# Output_amplifier.net
KiCad netlist of a schematic drawn in Altium Designer
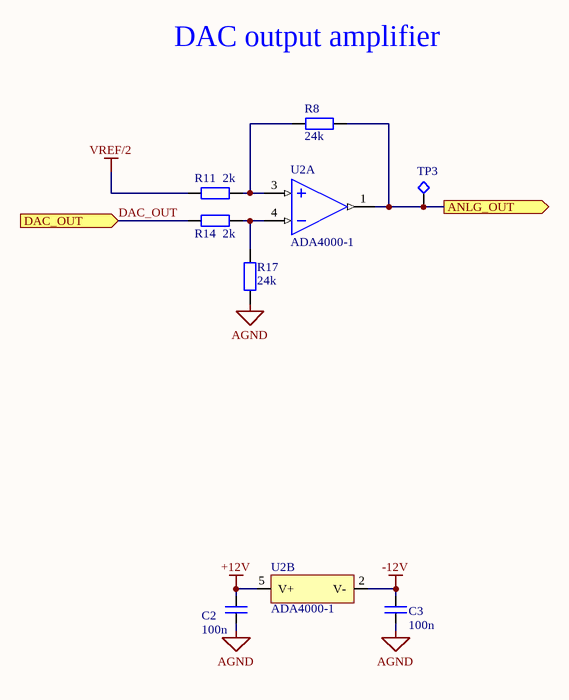
[diagram p0: Output_amplifier.SchDoc]

(export (version "E")
  (design (tool "Eeschema 10.0.6"))
  (components
    (comp (ref "C2")
      (value "100n")
      (footprint "C_0603")
      (description "Generic capacitor")
      (libsource (lib "DAQ_REV_B") (part "Capacitor"))
    )
    (comp (ref "C3")
      (value "100n")
      (footprint "C_0603")
      (description "Generic capacitor")
      (libsource (lib "DAQ_REV_B") (part "Capacitor"))
    )
    (comp (ref "R8")
      (value "24k")
      (footprint "R_0603")
      (description "Generic resistor")
      (libsource (lib "DAQ_REV_B") (part "Resistor"))
    )
    (comp (ref "R11")
      (value "2k")
      (footprint "R_0603")
      (description "Generic resistor")
      (libsource (lib "DAQ_REV_B") (part "Resistor"))
    )
    (comp (ref "R14")
      (value "2k")
      (footprint "R_0603")
      (description "Generic resistor")
      (libsource (lib "DAQ_REV_B") (part "Resistor"))
    )
    (comp (ref "R17")
      (value "24k")
      (footprint "R_0603")
      (description "Generic resistor")
      (libsource (lib "DAQ_REV_B") (part "Resistor"))
    )
    (comp (ref "TP3")
      (value "testpoint")
      (footprint "TP1_FULL")
      (description "testpoint 1.5mm diameter no hole")
      (fields (field (name "PART NUMBER") "XXC0006"))
      (libsource (lib "DAQ_REV_B") (part "Test Point"))
    )
    (comp (ref "U2")
      (value "ADA4000-1")
      (footprint "SOT23-5")
      (description "Operational Amplifier, Single, 1 Amplifier, 5 MHz, 20 V/µs, ± 4V to ± 18V, TSOT, 5 Pins")
      (fields (field (name "PART NUMBER") "XOG0003") (field (name "MANUFACTURER") "Analog devices"))
      (libsource (lib "DAQ_REV_B") (part "ADA4000-1"))
    )
  )
  (nets
    (net (code "1") (name "+12V") (class "Default")
      (node (ref "C2") (pin "1") (pinfunction "1_1") (pintype "passive"))
      (node (ref "U2") (pin "5") (pinfunction "V+_5") (pintype "power_in"))
    )
    (net (code "2") (name "-12V") (class "Default")
      (node (ref "C3") (pin "1") (pinfunction "1_1") (pintype "passive"))
      (node (ref "U2") (pin "2") (pinfunction "V-_2") (pintype "power_in"))
    )
    (net (code "3") (name "/ANLG_OUT") (class "Default")
      (node (ref "R8") (pin "2") (pintype "passive"))
      (node (ref "TP3") (pin "1") (pinfunction "1_1") (pintype "passive"))
      (node (ref "U2") (pin "1") (pinfunction "OUT_1") (pintype "output"))
    )
    (net (code "4") (name "/DAC_OUT") (class "Default") (node (ref "R14") (pin "1") (pintype "passive")))
    (net (code "5") (name "AGND") (class "Default")
      (node (ref "C2") (pin "2") (pinfunction "2_2") (pintype "passive"))
      (node (ref "C3") (pin "2") (pinfunction "2_2") (pintype "passive"))
      (node (ref "R17") (pin "1") (pintype "passive"))
    )
    (net (code "6") (name "Net-(U2A-IN+)") (class "Default")
      (node (ref "R11") (pin "2") (pintype "passive"))
      (node (ref "R8") (pin "1") (pintype "passive"))
      (node (ref "U2") (pin "3") (pinfunction "IN+_3") (pintype "input"))
    )
    (net (code "7") (name "Net-(U2A-IN-)") (class "Default")
      (node (ref "R14") (pin "2") (pintype "passive"))
      (node (ref "R17") (pin "2") (pintype "passive"))
      (node (ref "U2") (pin "4") (pinfunction "IN-_4") (pintype "input"))
    )
    (net (code "8") (name "VREF{slash}2") (class "Default") (node (ref "R11") (pin "1") (pintype "passive")))
  )
)
